# HV_Amp_Discrete.net
KiCad netlist of a schematic drawn in Altium Designer
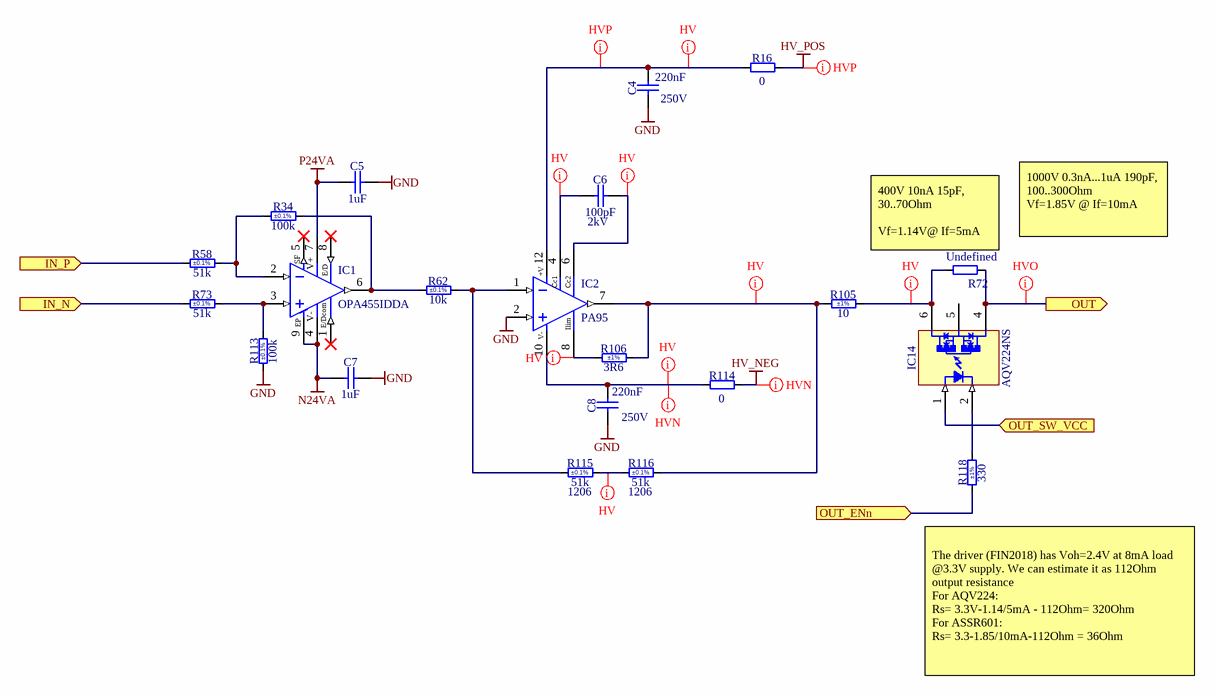
[diagram p0: HV_Amp_Discrete.SchDoc]

(export (version "E")
  (design (tool "Eeschema 10.0.6"))
  (components
    (comp (ref "C4")
      (value "220nF")
      (footprint "CAPC4532X165N")
      (description "Non-polarised capacitor")
      (fields
        (field (name "PART NUMBER") "CC1812_220NF_250V_10%_X7R_FT-CAP")
        (field (name "VOLTAGE") "250V")
        (field (name "TOLERANCE") "±10%")
        (field (name "AUTHOR") "CERN DEM JLC")
      )
      (libsource (lib "Capacitors") (part "Capacitor - non polarized"))
    )
    (comp (ref "C5")
      (value "1uF")
      (footprint "CAPC1608X87N")
      (description "Non-polarised capacitor")
      (fields
        (field (name "PART NUMBER") "CC0603_1UF_50V_10%_X5R")
        (field (name "VOLTAGE") "50V")
        (field (name "AUTHOR") "CERN DEM JMW")
      )
      (libsource (lib "Capacitors") (part "Capacitor - non polarized"))
    )
    (comp (ref "C6")
      (value "100pF")
      (footprint "CAPC4620X203N")
      (description "Non-polarised capacitor")
      (fields
        (field (name "PART NUMBER") "CC1808_100PF_2KV_5%_C0G")
        (field (name "VOLTAGE") "2kV")
        (field (name "TOLERANCE") "±5%")
        (field (name "AUTHOR") "CERN DEM JLC")
      )
      (libsource (lib "Capacitors") (part "Capacitor - non polarized"))
    )
    (comp (ref "C7")
      (value "1uF")
      (footprint "CAPC1608X87N")
      (description "Non-polarised capacitor")
      (fields
        (field (name "PART NUMBER") "CC0603_1UF_50V_10%_X5R")
        (field (name "VOLTAGE") "50V")
        (field (name "AUTHOR") "CERN DEM JMW")
      )
      (libsource (lib "Capacitors") (part "Capacitor - non polarized"))
    )
    (comp (ref "C8")
      (value "220nF")
      (footprint "CAPC4532X165N")
      (description "Non-polarised capacitor")
      (fields
        (field (name "PART NUMBER") "CC1812_220NF_250V_10%_X7R_FT-CAP")
        (field (name "VOLTAGE") "250V")
        (field (name "TOLERANCE") "±10%")
        (field (name "AUTHOR") "CERN DEM JLC")
      )
      (libsource (lib "Capacitors") (part "Capacitor - non polarized"))
    )
    (comp (ref "IC1")
      (value "OPA455IDDA")
      (footprint "SOIC127P600X170-9N-R249X300")
      (description "High-Voltage (150V), High-Current (50mA) Operational Amplifier, G=1 Stable")
      (fields (field (name "MANUFACTURER") "TEXAS INSTRUMENTS") (field (name "AUTHOR") "GK"))
      (libsource (lib "ICs_Analog_Interfaces") (part "OA_OPA455"))
    )
    (comp (ref "IC2")
      (value "PA95")
      (footprint "APEX_PA95_hflip")
      (description "High Voltage Power Operational Amplifier")
      (fields
        (field (name "PART NUMBER") "PA95_hflip")
        (field (name "MANUFACTURER") "APEX")
        (field (name "AUTHOR") "GK")
      )
      (libsource (lib "ICs_Analog_Interfaces") (part "OA_PA95"))
    )
    (comp (ref "IC14")
      (value "AQV224NS")
      (footprint "PANASONIC_AQV22(SOP)")
      (description "PhotoMOS Relay 400V 40mA")
      (fields (field (name "MANUFACTURER") "PANASONIC") (field (name "AUTHOR") "GK"))
      (libsource (lib "Optoisolators") (part "OPTOMOS_AQV224NS"))
    )
    (comp (ref "R16")
      (value "0")
      (footprint "RESC1608X55N")
      (description "Resistor")
      (fields
        (field (name "PART NUMBER") "R0603_0R_JUMPER")
        (field (name "MANUFACTURER") "GENERIC")
        (field (name "AUTHOR") "CERN DEM JLC")
      )
      (libsource (lib "Resistors") (part "Resistor"))
    )
    (comp (ref "R34")
      (value "100k")
      (footprint "RESC1608X55N")
      (description "Resistor - 0.1%")
      (fields
        (field (name "TOLERANCE") "±0.1%")
        (field (name "PART NUMBER") "R0603_100K_0.1%_0.063W_10PPM")
        (field (name "POWER") "0.063W")
        (field (name "AUTHOR") "CERN DEM JLC")
      )
      (libsource (lib "Resistors") (part "Resistor - 0.1%"))
    )
    (comp (ref "R58")
      (value "51k")
      (footprint "RESC2012X60N")
      (description "Resistor - 0.1%")
      (fields
        (field (name "TOLERANCE") "±0.1%")
        (field (name "PART NUMBER") "R0805_51K_0.1%_0.125W_10PPM")
        (field (name "POWER") "0.125W")
        (field (name "AUTHOR") "CERN DEM BC")
      )
      (libsource (lib "Resistors") (part "Resistor - 0.1%"))
    )
    (comp (ref "R62")
      (value "10k")
      (footprint "RESC1608X64N")
      (description "Resistor - 0.1%")
      (fields
        (field (name "TOLERANCE") "±0.1%")
        (field (name "PART NUMBER") "R0603_10K_0.1%_0.1W_25PPM")
        (field (name "POWER") "0.1W")
        (field (name "AUTHOR") "CERN DEM JMW")
      )
      (libsource (lib "Resistors") (part "Resistor - 0.1%"))
    )
    (comp (ref "R72")
      (value "Undefined")
      (footprint "RESC3216X65N")
      (description "Resistor")
      (fields (field (name "PART NUMBER") "R1206_NO-VALUE") (field (name "AUTHOR") "CERN DEM JLC"))
      (libsource (lib "Resistors") (part "Resistor"))
    )
    (comp (ref "R73")
      (value "51k")
      (footprint "RESC2012X60N")
      (description "Resistor - 0.1%")
      (fields
        (field (name "TOLERANCE") "±0.1%")
        (field (name "PART NUMBER") "R0805_51K_0.1%_0.125W_10PPM")
        (field (name "POWER") "0.125W")
        (field (name "AUTHOR") "CERN DEM BC")
      )
      (libsource (lib "Resistors") (part "Resistor - 0.1%"))
    )
    (comp (ref "R105")
      (value "10")
      (footprint "RESC3216X65N")
      (description "Resistor - 1%")
      (fields
        (field (name "TOLERANCE") "±1%")
        (field (name "PART NUMBER") "R1206_10R_1%_0.25W_200PPM")
        (field (name "POWER") "0.25W")
        (field (name "AUTHOR") "CERN DEM JLC")
      )
      (libsource (lib "Resistors") (part "Resistor - 1%"))
    )
    (comp (ref "R106")
      (value "3R6")
      (footprint "RESC1608X55N")
      (description "Resistor - 1%")
      (fields
        (field (name "TOLERANCE") "±1%")
        (field (name "PART NUMBER") "R0603_3R6_1%_0.1W_200PPM")
        (field (name "POWER") "0.1W")
        (field (name "AUTHOR") "CERN DEM JLC")
      )
      (libsource (lib "Resistors") (part "Resistor - 1%"))
    )
    (comp (ref "R113")
      (value "100k")
      (footprint "RESC1608X55N")
      (description "Resistor - 0.1%")
      (fields
        (field (name "TOLERANCE") "±0.1%")
        (field (name "PART NUMBER") "R0603_100K_0.1%_0.063W_10PPM")
        (field (name "POWER") "0.063W")
        (field (name "AUTHOR") "CERN DEM JLC")
      )
      (libsource (lib "Resistors") (part "Resistor - 0.1%"))
    )
    (comp (ref "R114")
      (value "0")
      (footprint "RESC1608X55N")
      (description "Resistor")
      (fields
        (field (name "PART NUMBER") "R0603_0R_JUMPER")
        (field (name "MANUFACTURER") "GENERIC")
        (field (name "AUTHOR") "CERN DEM JLC")
      )
      (libsource (lib "Resistors") (part "Resistor"))
    )
    (comp (ref "R115")
      (value "51k")
      (footprint "RESC3216X65N")
      (description "Resistor - 0.1%")
      (fields
        (field (name "TOLERANCE") "±0.1%")
        (field (name "PART NUMBER") "R1206_51K_0.1%_0.25W_25PPM")
        (field (name "POWER") "0.25W")
        (field (name "CASE") "1206")
        (field (name "AUTHOR") "CERN DEM JLC")
      )
      (libsource (lib "Resistors") (part "Resistor - 0.1%"))
    )
    (comp (ref "R116")
      (value "51k")
      (footprint "RESC3216X65N")
      (description "Resistor - 0.1%")
      (fields
        (field (name "TOLERANCE") "±0.1%")
        (field (name "PART NUMBER") "R1206_51K_0.1%_0.25W_25PPM")
        (field (name "POWER") "0.25W")
        (field (name "CASE") "1206")
        (field (name "AUTHOR") "CERN DEM JLC")
      )
      (libsource (lib "Resistors") (part "Resistor - 0.1%"))
    )
    (comp (ref "R118")
      (value "330")
      (footprint "RESC1005X40N")
      (description "Resistor - 1%")
      (fields
        (field (name "TOLERANCE") "±1%")
        (field (name "PART NUMBER") "R0402_330R_1%_0.0625W_100PPM")
        (field (name "POWER") "0.0625W")
        (field (name "AUTHOR") "CERN DEM JLC")
      )
      (libsource (lib "Resistors") (part "Resistor - 1%"))
    )
  )
  (nets
    (net (code "1") (name "/IN_N") (class "Default")
      (node (ref "R73") (pin "1") (pinfunction "1_1") (pintype "passive"))
    )
    (net (code "2") (name "/IN_P") (class "Default")
      (node (ref "R58") (pin "1") (pinfunction "1_1") (pintype "passive"))
    )
    (net (code "3") (name "/OUT") (class "Default")
      (node (ref "IC14") (pin "4") (pinfunction "4_4") (pintype "passive"))
      (node (ref "R72") (pin "2") (pinfunction "2_2") (pintype "passive"))
    )
    (net (code "4") (name "/OUT_ENn") (class "Default")
      (node (ref "R118") (pin "1") (pinfunction "1_1") (pintype "passive"))
    )
    (net (code "5") (name "/OUT_SW_VCC") (class "Default")
      (node (ref "IC14") (pin "1") (pinfunction "A_1") (pintype "input"))
    )
    (net (code "6") (name "GND") (class "Default")
      (node (ref "C4") (pin "1") (pinfunction "1_1") (pintype "passive"))
      (node (ref "C5") (pin "2") (pinfunction "2_2") (pintype "passive"))
      (node (ref "C7") (pin "2") (pinfunction "2_2") (pintype "passive"))
      (node (ref "C8") (pin "1") (pinfunction "1_1") (pintype "passive"))
      (node (ref "IC2") (pin "2") (pinfunction "IN+_2") (pintype "input"))
      (node (ref "R113") (pin "1") (pinfunction "1_1") (pintype "passive"))
    )
    (net (code "7") (name "HV_NEG") (class "Default")
      (node (ref "R114") (pin "2") (pinfunction "2_2") (pintype "passive"))
    )
    (net (code "8") (name "HV_POS") (class "Default")
      (node (ref "R16") (pin "2") (pinfunction "2_2") (pintype "passive"))
    )
    (net (code "9") (name "N24VA") (class "Default")
      (node (ref "C7") (pin "1") (pinfunction "1_1") (pintype "passive"))
      (node (ref "IC1") (pin "4") (pinfunction "V-_4") (pintype "power_in"))
      (node (ref "IC1") (pin "9") (pinfunction "Exposed_Pad_9") (pintype "power_in"))
    )
    (net (code "10") (name "Net-(IC1-IN+)") (class "Default")
      (node (ref "IC1") (pin "3") (pinfunction "IN+_3") (pintype "input"))
      (node (ref "R113") (pin "2") (pinfunction "2_2") (pintype "passive"))
      (node (ref "R73") (pin "2") (pinfunction "2_2") (pintype "passive"))
    )
    (net (code "11") (name "Net-(IC1-IN-)") (class "Default")
      (node (ref "IC1") (pin "2") (pinfunction "IN-_2") (pintype "input"))
      (node (ref "R34") (pin "1") (pinfunction "1_1") (pintype "passive"))
      (node (ref "R58") (pin "2") (pinfunction "2_2") (pintype "passive"))
    )
    (net (code "12") (name "Net-(IC1-OUT)") (class "Default")
      (node (ref "IC1") (pin "6") (pinfunction "OUT_6") (pintype "output"))
      (node (ref "R34") (pin "2") (pinfunction "2_2") (pintype "passive"))
      (node (ref "R62") (pin "1") (pinfunction "1_1") (pintype "passive"))
    )
    (net (code "13") (name "Net-(IC2-+Vs)") (class "Default")
      (node (ref "C4") (pin "2") (pinfunction "2_2") (pintype "passive"))
      (node (ref "IC2") (pin "12") (pinfunction "+Vs_12") (pintype "power_in"))
      (node (ref "R16") (pin "1") (pinfunction "1_1") (pintype "passive"))
    )
    (net (code "14") (name "Net-(IC2--Vs)") (class "Default")
      (node (ref "C8") (pin "2") (pinfunction "2_2") (pintype "passive"))
      (node (ref "IC2") (pin "10") (pinfunction "-Vs_10") (pintype "power_in"))
      (node (ref "R114") (pin "1") (pinfunction "1_1") (pintype "passive"))
    )
    (net (code "15") (name "Net-(IC2-Cc1)") (class "Default")
      (node (ref "C6") (pin "1") (pinfunction "1_1") (pintype "passive"))
      (node (ref "IC2") (pin "4") (pinfunction "Cc1_4") (pintype "passive"))
    )
    (net (code "16") (name "Net-(IC2-Cc2)") (class "Default")
      (node (ref "C6") (pin "2") (pinfunction "2_2") (pintype "passive"))
      (node (ref "IC2") (pin "6") (pinfunction "Cc2_6") (pintype "passive"))
    )
    (net (code "17") (name "Net-(IC2-ILIM)") (class "Default")
      (node (ref "IC2") (pin "8") (pinfunction "ILIM_8") (pintype "passive"))
      (node (ref "R106") (pin "1") (pinfunction "1_1") (pintype "passive"))
    )
    (net (code "18") (name "Net-(IC2-IN-)") (class "Default")
      (node (ref "IC2") (pin "1") (pinfunction "IN-_1") (pintype "input"))
      (node (ref "R115") (pin "1") (pinfunction "1_1") (pintype "passive"))
      (node (ref "R62") (pin "2") (pinfunction "2_2") (pintype "passive"))
    )
    (net (code "19") (name "Net-(IC2-OUT)") (class "Default")
      (node (ref "IC2") (pin "7") (pinfunction "OUT_7") (pintype "output"))
      (node (ref "R105") (pin "1") (pinfunction "1_1") (pintype "passive"))
      (node (ref "R106") (pin "2") (pinfunction "2_2") (pintype "passive"))
      (node (ref "R116") (pin "2") (pinfunction "2_2") (pintype "passive"))
    )
    (net (code "20") (name "Net-(IC14-K)") (class "Default")
      (node (ref "IC14") (pin "2") (pinfunction "K_2") (pintype "input"))
      (node (ref "R118") (pin "2") (pinfunction "2_2") (pintype "passive"))
    )
    (net (code "21") (name "Net-(IC14-Pad6)") (class "Default")
      (node (ref "IC14") (pin "6") (pinfunction "6_6") (pintype "passive"))
      (node (ref "R105") (pin "2") (pinfunction "2_2") (pintype "passive"))
      (node (ref "R72") (pin "1") (pinfunction "1_1") (pintype "passive"))
    )
    (net (code "22") (name "Net-(R115-Pad2)") (class "Default")
      (node (ref "R115") (pin "2") (pinfunction "2_2") (pintype "passive"))
      (node (ref "R116") (pin "1") (pinfunction "1_1") (pintype "passive"))
    )
    (net (code "23") (name "P24VA") (class "Default")
      (node (ref "C5") (pin "1") (pinfunction "1_1") (pintype "passive"))
      (node (ref "IC1") (pin "7") (pinfunction "V+_7") (pintype "power_in"))
    )
    (net (code "24") (name "unconnected-(IC1-E{slash}B-Pad8)") (class "Default")
      (node (ref "IC1") (pin "8") (pinfunction "E/B_8") (pintype "input+no_connect"))
    )
    (net (code "25") (name "unconnected-(IC1-E{slash}Dcommon-Pad1)") (class "Default")
      (node (ref "IC1") (pin "1") (pinfunction "E/Dcommon_1") (pintype "input+no_connect"))
    )
    (net (code "26") (name "unconnected-(IC1-Status_Flag-Pad5)") (class "Default")
      (node (ref "IC1") (pin "5") (pinfunction "Status_Flag_5") (pintype "output+no_connect"))
    )
    (net (code "27") (name "unconnected-(IC14-Pad5)") (class "Default")
      (node (ref "IC14") (pin "5") (pinfunction "5_5") (pintype "passive"))
    )
  )
)
